# ESP32_with_USBC.net
KiCad netlist of a schematic drawn in Altium Designer
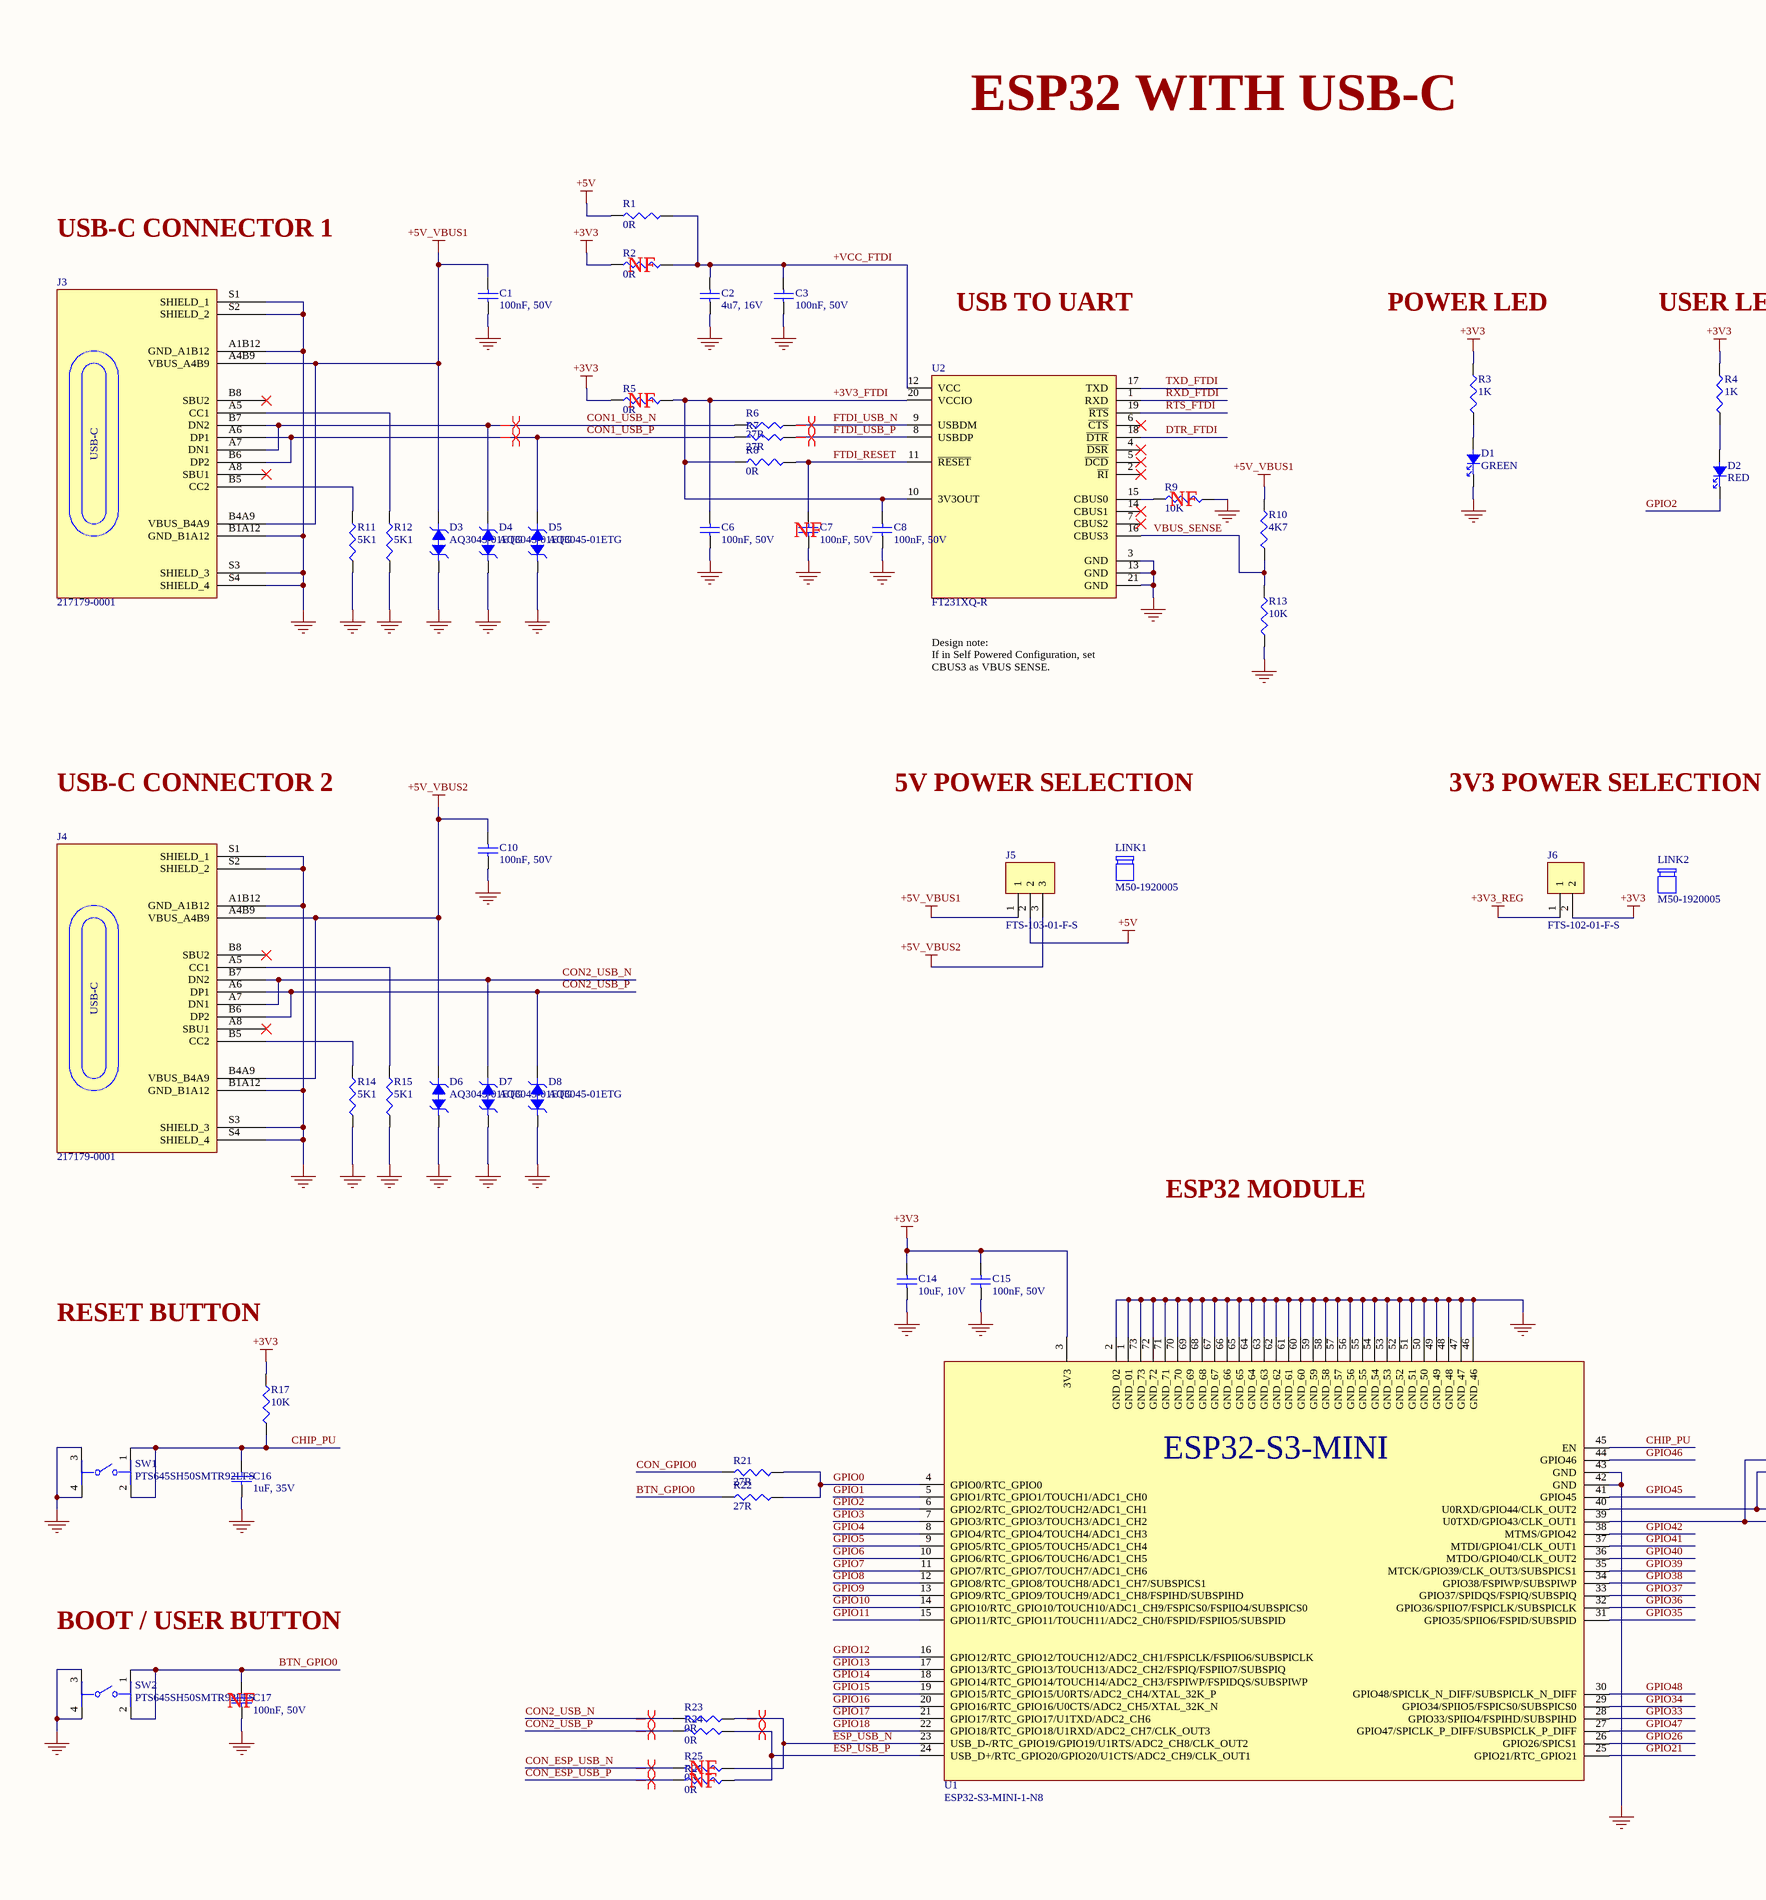
[diagram p0: ESP32 with USBC.SchDoc, left]
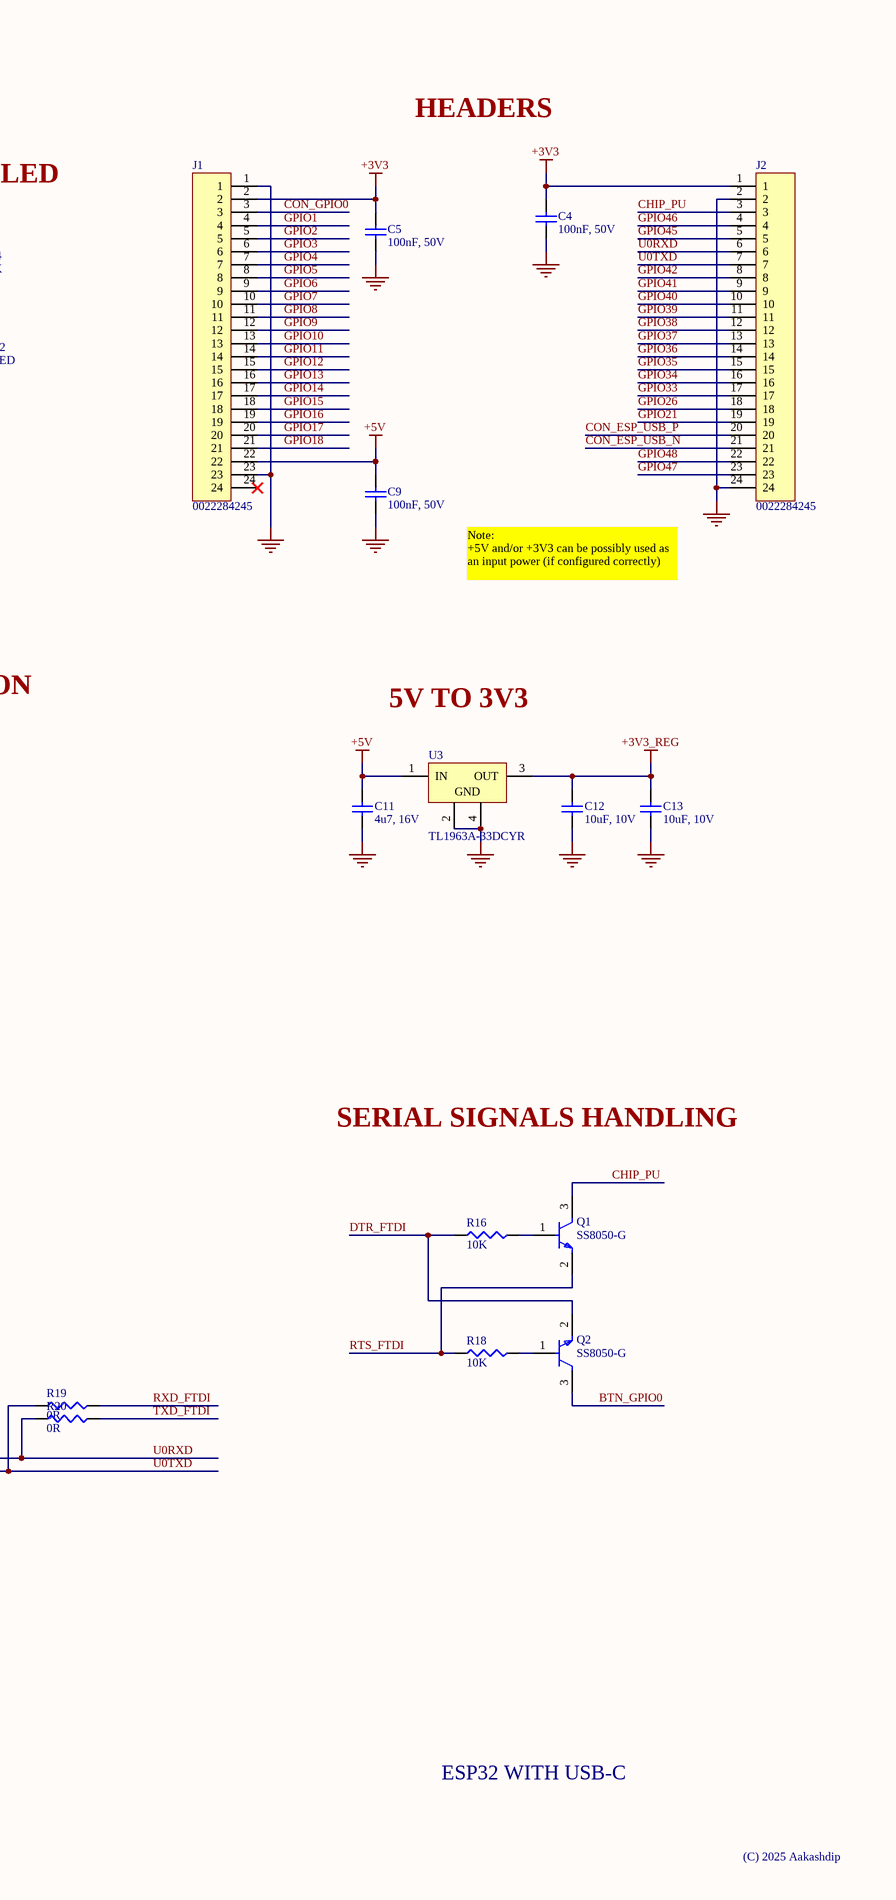
[diagram p1: ESP32 with USBC.SchDoc, right]

(export (version "E")
  (design (tool "Eeschema 10.0.6"))
  (components
    (comp (ref "C1")
      (value "100nF, 50V")
      (footprint "CAPC1005X55N")
      (description "CAP CER 0.1UF 50V X7R 0402")
      (fields
        (field (name "MANUFACTURER") "Samsung")
        (field (name "MANUFACTURER PART NUMBER") "CL05B104KB54PNC")
      )
      (libsource (lib "Schlib") (part "CL05B104KB54PNC"))
    )
    (comp (ref "C2")
      (value "4u7, 16V")
      (footprint "CAPC1005X55N")
      (description "CAP CER 4.7UF 16V X5R 0402")
      (fields
        (field (name "MANUFACTURER") "Samsung")
        (field (name "MANUFACTURER PART NUMBER") "CL05A475MO5NUNC")
      )
      (libsource (lib "Schlib") (part "CL05A475MO5NUNC"))
    )
    (comp (ref "C3")
      (value "100nF, 50V")
      (footprint "CAPC1005X55N")
      (description "CAP CER 0.1UF 50V X7R 0402")
      (fields
        (field (name "MANUFACTURER") "Samsung")
        (field (name "MANUFACTURER PART NUMBER") "CL05B104KB54PNC")
      )
      (libsource (lib "Schlib") (part "CL05B104KB54PNC"))
    )
    (comp (ref "C4")
      (value "100nF, 50V")
      (footprint "CAPC1005X55N")
      (description "CAP CER 0.1UF 50V X7R 0402")
      (fields
        (field (name "MANUFACTURER") "Samsung")
        (field (name "MANUFACTURER PART NUMBER") "CL05B104KB54PNC")
      )
      (libsource (lib "Schlib") (part "CL05B104KB54PNC"))
    )
    (comp (ref "C5")
      (value "100nF, 50V")
      (footprint "CAPC1005X55N")
      (description "CAP CER 0.1UF 50V X7R 0402")
      (fields
        (field (name "MANUFACTURER") "Samsung")
        (field (name "MANUFACTURER PART NUMBER") "CL05B104KB54PNC")
      )
      (libsource (lib "Schlib") (part "CL05B104KB54PNC"))
    )
    (comp (ref "C6")
      (value "100nF, 50V")
      (footprint "CAPC1005X55N")
      (description "CAP CER 0.1UF 50V X7R 0402")
      (fields
        (field (name "MANUFACTURER") "Samsung")
        (field (name "MANUFACTURER PART NUMBER") "CL05B104KB54PNC")
      )
      (libsource (lib "Schlib") (part "CL05B104KB54PNC"))
    )
    (comp (ref "C7")
      (value "100nF, 50V")
      (footprint "CAPC1005X55N")
      (description "CAP CER 0.1UF 50V X7R 0402")
      (fields
        (field (name "MANUFACTURER") "Samsung")
        (field (name "MANUFACTURER PART NUMBER") "CL05B104KB54PNC")
      )
      (libsource (lib "Schlib") (part "CL05B104KB54PNC"))
    )
    (comp (ref "C8")
      (value "100nF, 50V")
      (footprint "CAPC1005X55N")
      (description "CAP CER 0.1UF 50V X7R 0402")
      (fields
        (field (name "MANUFACTURER") "Samsung")
        (field (name "MANUFACTURER PART NUMBER") "CL05B104KB54PNC")
      )
      (libsource (lib "Schlib") (part "CL05B104KB54PNC"))
    )
    (comp (ref "C9")
      (value "100nF, 50V")
      (footprint "CAPC1005X55N")
      (description "CAP CER 0.1UF 50V X7R 0402")
      (fields
        (field (name "MANUFACTURER") "Samsung")
        (field (name "MANUFACTURER PART NUMBER") "CL05B104KB54PNC")
      )
      (libsource (lib "Schlib") (part "CL05B104KB54PNC"))
    )
    (comp (ref "C10")
      (value "100nF, 50V")
      (footprint "CAPC1005X55N")
      (description "CAP CER 0.1UF 50V X7R 0402")
      (fields
        (field (name "MANUFACTURER") "Samsung")
        (field (name "MANUFACTURER PART NUMBER") "CL05B104KB54PNC")
      )
      (libsource (lib "Schlib") (part "CL05B104KB54PNC"))
    )
    (comp (ref "C11")
      (value "4u7, 16V")
      (footprint "CAPC1005X55N")
      (description "CAP CER 4.7UF 16V X5R 0402")
      (fields
        (field (name "MANUFACTURER") "Samsung")
        (field (name "MANUFACTURER PART NUMBER") "CL05A475MO5NUNC")
      )
      (libsource (lib "Schlib") (part "CL05A475MO5NUNC"))
    )
    (comp (ref "C12")
      (value "10uF, 10V")
      (footprint "CAPC1005X55N")
      (description "CAP CER 10UF 10V X5R 0402")
      (fields
        (field (name "MANUFACTURER") "Samsung")
        (field (name "MANUFACTURER PART NUMBER") "CL05A106MP8NUB8")
      )
      (libsource (lib "Schlib") (part "CL05A106MP8NUB8"))
    )
    (comp (ref "C13")
      (value "10uF, 10V")
      (footprint "CAPC1005X55N")
      (description "CAP CER 10UF 10V X5R 0402")
      (fields
        (field (name "MANUFACTURER") "Samsung")
        (field (name "MANUFACTURER PART NUMBER") "CL05A106MP8NUB8")
      )
      (libsource (lib "Schlib") (part "CL05A106MP8NUB8"))
    )
    (comp (ref "C14")
      (value "10uF, 10V")
      (footprint "CAPC1005X55N")
      (description "CAP CER 10UF 10V X5R 0402")
      (fields
        (field (name "MANUFACTURER") "Samsung")
        (field (name "MANUFACTURER PART NUMBER") "CL05A106MP8NUB8")
      )
      (libsource (lib "Schlib") (part "CL05A106MP8NUB8"))
    )
    (comp (ref "C15")
      (value "100nF, 50V")
      (footprint "CAPC1005X55N")
      (description "CAP CER 0.1UF 50V X7R 0402")
      (fields
        (field (name "MANUFACTURER") "Samsung")
        (field (name "MANUFACTURER PART NUMBER") "CL05B104KB54PNC")
      )
      (libsource (lib "Schlib") (part "CL05B104KB54PNC"))
    )
    (comp (ref "C16")
      (value "1uF, 35V")
      (footprint "CAPC1005X55N")
      (description "CAP CER 1UF 35V X5R 0402")
      (fields
        (field (name "MANUFACTURER") "Samsung")
        (field (name "MANUFACTURER PART NUMBER") "CL05A105KL5NRNC")
      )
      (libsource (lib "Schlib") (part "CL05A105KL5NRNC"))
    )
    (comp (ref "C17")
      (value "100nF, 50V")
      (footprint "CAPC1005X55N")
      (description "CAP CER 0.1UF 50V X7R 0402")
      (fields
        (field (name "MANUFACTURER") "Samsung")
        (field (name "MANUFACTURER PART NUMBER") "CL05B104KB54PNC")
      )
      (libsource (lib "Schlib") (part "CL05B104KB54PNC"))
    )
    (comp (ref "D1")
      (value "GREEN")
      (footprint "LED0402G")
      (description "LED YLW-GRN 0402 SMD")
      (fields
        (field (name "MANUFACTURER") "Vishay")
        (field (name "MANUFACTURER PART NUMBER") "VLMG1500-GS08")
      )
      (libsource (lib "Schlib") (part "VLMG1500-GS08"))
    )
    (comp (ref "D2")
      (value "RED")
      (footprint "LED0402R")
      (description "LED RED 0402 SMD")
      (fields
        (field (name "MANUFACTURER") "Vishay")
        (field (name "MANUFACTURER PART NUMBER") "VLMS1500-GS08")
      )
      (libsource (lib "Schlib") (part "VLMS1500-GS08"))
    )
    (comp (ref "D3")
      (value "AQ3045-01ETG")
      (footprint "SOD882")
      (description "TVS DIODE 5.3VWM 12VC SOD882")
      (fields (field (name "MANUFACTURER") "Littelfuse") (field (name "LCSC PART NUMBER") "C3710326"))
      (libsource (lib "Schlib") (part "AQ3045-01ETG"))
    )
    (comp (ref "D4")
      (value "AQ3045-01ETG")
      (footprint "SOD882")
      (description "TVS DIODE 5.3VWM 12VC SOD882")
      (fields (field (name "MANUFACTURER") "Littelfuse") (field (name "LCSC PART NUMBER") "C3710326"))
      (libsource (lib "Schlib") (part "AQ3045-01ETG"))
    )
    (comp (ref "D5")
      (value "AQ3045-01ETG")
      (footprint "SOD882")
      (description "TVS DIODE 5.3VWM 12VC SOD882")
      (fields (field (name "MANUFACTURER") "Littelfuse") (field (name "LCSC PART NUMBER") "C3710326"))
      (libsource (lib "Schlib") (part "AQ3045-01ETG"))
    )
    (comp (ref "D6")
      (value "AQ3045-01ETG")
      (footprint "SOD882")
      (description "TVS DIODE 5.3VWM 12VC SOD882")
      (fields (field (name "MANUFACTURER") "Littelfuse") (field (name "LCSC PART NUMBER") "C3710326"))
      (libsource (lib "Schlib") (part "AQ3045-01ETG"))
    )
    (comp (ref "D7")
      (value "AQ3045-01ETG")
      (footprint "SOD882")
      (description "TVS DIODE 5.3VWM 12VC SOD882")
      (fields (field (name "MANUFACTURER") "Littelfuse") (field (name "LCSC PART NUMBER") "C3710326"))
      (libsource (lib "Schlib") (part "AQ3045-01ETG"))
    )
    (comp (ref "D8")
      (value "AQ3045-01ETG")
      (footprint "SOD882")
      (description "TVS DIODE 5.3VWM 12VC SOD882")
      (fields (field (name "MANUFACTURER") "Littelfuse") (field (name "LCSC PART NUMBER") "C3710326"))
      (libsource (lib "Schlib") (part "AQ3045-01ETG"))
    )
    (comp (ref "J1")
      (value "0022284245")
      (footprint "HDR_1X24_2.54MM")
      (description "CONN HEADER VERT 24POS 2.54MM")
      (fields (field (name "MANUFACTURER") "Molex") (field (name "LCSC PART NUMBER") "C7145888"))
      (libsource (lib "Schlib") (part "0022284245"))
    )
    (comp (ref "J2")
      (value "0022284245")
      (footprint "HDR_1X24_2.54MM")
      (description "CONN HEADER VERT 24POS 2.54MM")
      (fields (field (name "MANUFACTURER") "Molex") (field (name "LCSC PART NUMBER") "C7145888"))
      (libsource (lib "") (part "0022284245_1"))
    )
    (comp (ref "J3")
      (value "217179-0001")
      (footprint "FP-2171790001-MFG")
      (description "CONN RCP USB2.0 TYP C 24P SMD RA")
      (fields (field (name "MANUFACTURER") "Molex") (field (name "LCSC PART NUMBER") "C3197684"))
      (libsource (lib "Schlib") (part "217179-0001"))
    )
    (comp (ref "J4")
      (value "217179-0001")
      (footprint "FP-2171790001-MFG")
      (description "CONN RCP USB2.0 TYP C 24P SMD RA")
      (fields (field (name "MANUFACTURER") "Molex") (field (name "LCSC PART NUMBER") "C3197684"))
      (libsource (lib "Schlib") (part "217179-0001"))
    )
    (comp (ref "J5")
      (value "FTS-103-01-F-S")
      (footprint "HDR_1X3_1.27MM")
      (description "CONN HEADER VERT 3POS 1.27MM")
      (fields (field (name "MANUFACTURER") "Samtec") (field (name "LCSC PART NUMBER") "C3333578"))
      (libsource (lib "Schlib") (part "FTS-103-01-F-S"))
    )
    (comp (ref "J6")
      (value "FTS-102-01-F-S")
      (footprint "HDR_1X2_1.27MM")
      (description "CONN HEADER VERT 2POS 1.27MM")
      (fields (field (name "MANUFACTURER") "Samtec") (field (name "LCSC PART NUMBER") "C6045317"))
      (libsource (lib "Schlib") (part "FTS-102-01-F-S"))
    )
    (comp (ref "LINK1")
      (value "M50-1920005")
      (description "CONN SHUNT 1.27MM RED")
      (fields (field (name "MANUFACTURER") "Harwin") (field (name "LCSC PART NUMBER") "C6985646"))
      (libsource (lib "Schlib") (part "M50-1920005"))
    )
    (comp (ref "LINK2")
      (value "M50-1920005")
      (description "CONN SHUNT 1.27MM RED")
      (fields (field (name "MANUFACTURER") "Harwin") (field (name "LCSC PART NUMBER") "C6985646"))
      (libsource (lib "Schlib") (part "M50-1920005"))
    )
    (comp (ref "Q1")
      (value "SS8050-G")
      (footprint "FP-SS8050-G-IPC_B")
      (description "TRANS NPN 25V 1.5A SOT23-3")
      (fields (field (name "MANUFACTURER") "Comchip") (field (name "LCSC PART NUMBER") "C164886"))
      (libsource (lib "Schlib") (part "SS8050-G"))
    )
    (comp (ref "Q2")
      (value "SS8050-G")
      (footprint "FP-SS8050-G-IPC_B")
      (description "TRANS NPN 25V 1.5A SOT23-3")
      (fields (field (name "MANUFACTURER") "Comchip") (field (name "LCSC PART NUMBER") "C164886"))
      (libsource (lib "Schlib") (part "SS8050-G"))
    )
    (comp (ref "R1")
      (value "0R")
      (footprint "RESC1005X37N")
      (description "RES 0 OHM JUMPER 1/16W 0402")
      (fields
        (field (name "MANUFACTURER") "Yageo")
        (field (name "MANUFACTURER PART NUMBER") "RC0402JR-070RL")
      )
      (libsource (lib "Schlib") (part "RC0402JR-070RL"))
    )
    (comp (ref "R2")
      (value "0R")
      (footprint "RESC1005X37N")
      (description "RES 0 OHM JUMPER 1/16W 0402")
      (fields
        (field (name "MANUFACTURER") "Yageo")
        (field (name "MANUFACTURER PART NUMBER") "RC0402JR-070RL")
      )
      (libsource (lib "Schlib") (part "RC0402JR-070RL"))
    )
    (comp (ref "R3")
      (value "1K")
      (footprint "RESC1005X37N")
      (description "RES 1K OHM 1% 1/16W 0402")
      (fields
        (field (name "MANUFACTURER") "Yageo")
        (field (name "MANUFACTURER PART NUMBER") "RC0402FR-071KL")
      )
      (libsource (lib "Schlib") (part "RC0402FR-071KL"))
    )
    (comp (ref "R4")
      (value "1K")
      (footprint "RESC1005X37N")
      (description "RES 1K OHM 1% 1/16W 0402")
      (fields
        (field (name "MANUFACTURER") "Yageo")
        (field (name "MANUFACTURER PART NUMBER") "RC0402FR-071KL")
      )
      (libsource (lib "Schlib") (part "RC0402FR-071KL"))
    )
    (comp (ref "R5")
      (value "0R")
      (footprint "RESC1005X37N")
      (description "RES 0 OHM JUMPER 1/16W 0402")
      (fields
        (field (name "MANUFACTURER") "Yageo")
        (field (name "MANUFACTURER PART NUMBER") "RC0402JR-070RL")
      )
      (libsource (lib "Schlib") (part "RC0402JR-070RL"))
    )
    (comp (ref "R6")
      (value "27R")
      (footprint "RESC1005X37N")
      (description "RES 27 OHM 1% 1/16W 0402")
      (fields
        (field (name "MANUFACTURER") "Yageo")
        (field (name "MANUFACTURER PART NUMBER") "RC0402FR-0727RL")
      )
      (libsource (lib "Schlib") (part "RC0402FR-0727RL"))
    )
    (comp (ref "R7")
      (value "27R")
      (footprint "RESC1005X37N")
      (description "RES 27 OHM 1% 1/16W 0402")
      (fields
        (field (name "MANUFACTURER") "Yageo")
        (field (name "MANUFACTURER PART NUMBER") "RC0402FR-0727RL")
      )
      (libsource (lib "Schlib") (part "RC0402FR-0727RL"))
    )
    (comp (ref "R8")
      (value "0R")
      (footprint "RESC1005X37N")
      (description "RES 0 OHM JUMPER 1/16W 0402")
      (fields
        (field (name "MANUFACTURER") "Yageo")
        (field (name "MANUFACTURER PART NUMBER") "RC0402JR-070RL")
      )
      (libsource (lib "Schlib") (part "RC0402JR-070RL"))
    )
    (comp (ref "R9")
      (value "10K")
      (footprint "RESC1005X37N")
      (description "RES SMD 10K OHM 1% 1/16W 0402")
      (fields
        (field (name "MANUFACTURER") "Yageo")
        (field (name "MANUFACTURER PART NUMBER") "AC0402FR-0710KL")
      )
      (libsource (lib "Schlib") (part "AC0402FR-0710KL"))
    )
    (comp (ref "R10")
      (value "4K7")
      (footprint "RESC1005X37N")
      (description "RES 4.7K OHM 1% 1/16W 0402")
      (fields
        (field (name "MANUFACTURER") "Yageo")
        (field (name "MANUFACTURER PART NUMBER") "RC0402FR-074K7L")
      )
      (libsource (lib "Schlib") (part "RC0402FR-074K7L"))
    )
    (comp (ref "R11")
      (value "5K1")
      (footprint "RESC1005X37N")
      (description "RES SMD 5.1K OHM 1% 1/16W 0402")
      (fields
        (field (name "MANUFACTURER") "Yageo")
        (field (name "MANUFACTURER PART NUMBER") "AC0402FR-075K1L")
      )
      (libsource (lib "Schlib") (part "AC0402FR-075K1L"))
    )
    (comp (ref "R12")
      (value "5K1")
      (footprint "RESC1005X37N")
      (description "RES SMD 5.1K OHM 1% 1/16W 0402")
      (fields
        (field (name "MANUFACTURER") "Yageo")
        (field (name "MANUFACTURER PART NUMBER") "AC0402FR-075K1L")
      )
      (libsource (lib "Schlib") (part "AC0402FR-075K1L"))
    )
    (comp (ref "R13")
      (value "10K")
      (footprint "RESC1005X37N")
      (description "RES SMD 10K OHM 1% 1/16W 0402")
      (fields
        (field (name "MANUFACTURER") "Yageo")
        (field (name "MANUFACTURER PART NUMBER") "AC0402FR-0710KL")
      )
      (libsource (lib "Schlib") (part "AC0402FR-0710KL"))
    )
    (comp (ref "R14")
      (value "5K1")
      (footprint "RESC1005X37N")
      (description "RES SMD 5.1K OHM 1% 1/16W 0402")
      (fields
        (field (name "MANUFACTURER") "Yageo")
        (field (name "MANUFACTURER PART NUMBER") "AC0402FR-075K1L")
      )
      (libsource (lib "Schlib") (part "AC0402FR-075K1L"))
    )
    (comp (ref "R15")
      (value "5K1")
      (footprint "RESC1005X37N")
      (description "RES SMD 5.1K OHM 1% 1/16W 0402")
      (fields
        (field (name "MANUFACTURER") "Yageo")
        (field (name "MANUFACTURER PART NUMBER") "AC0402FR-075K1L")
      )
      (libsource (lib "Schlib") (part "AC0402FR-075K1L"))
    )
    (comp (ref "R16")
      (value "10K")
      (footprint "RESC1005X37N")
      (description "RES SMD 10K OHM 1% 1/16W 0402")
      (fields
        (field (name "MANUFACTURER") "Yageo")
        (field (name "MANUFACTURER PART NUMBER") "AC0402FR-0710KL")
      )
      (libsource (lib "Schlib") (part "AC0402FR-0710KL"))
    )
    (comp (ref "R17")
      (value "10K")
      (footprint "RESC1005X37N")
      (description "RES SMD 10K OHM 1% 1/16W 0402")
      (fields
        (field (name "MANUFACTURER") "Yageo")
        (field (name "MANUFACTURER PART NUMBER") "AC0402FR-0710KL")
      )
      (libsource (lib "Schlib") (part "AC0402FR-0710KL"))
    )
    (comp (ref "R18")
      (value "10K")
      (footprint "RESC1005X37N")
      (description "RES SMD 10K OHM 1% 1/16W 0402")
      (fields
        (field (name "MANUFACTURER") "Yageo")
        (field (name "MANUFACTURER PART NUMBER") "AC0402FR-0710KL")
      )
      (libsource (lib "Schlib") (part "AC0402FR-0710KL"))
    )
    (comp (ref "R19")
      (value "0R")
      (footprint "RESC1005X37N")
      (description "RES 0 OHM JUMPER 1/16W 0402")
      (fields
        (field (name "MANUFACTURER") "Yageo")
        (field (name "MANUFACTURER PART NUMBER") "RC0402JR-070RL")
      )
      (libsource (lib "Schlib") (part "RC0402JR-070RL"))
    )
    (comp (ref "R20")
      (value "0R")
      (footprint "RESC1005X37N")
      (description "RES 0 OHM JUMPER 1/16W 0402")
      (fields
        (field (name "MANUFACTURER") "Yageo")
        (field (name "MANUFACTURER PART NUMBER") "RC0402JR-070RL")
      )
      (libsource (lib "Schlib") (part "RC0402JR-070RL"))
    )
    (comp (ref "R21")
      (value "27R")
      (footprint "RESC1005X37N")
      (description "RES 27 OHM 1% 1/16W 0402")
      (fields
        (field (name "MANUFACTURER") "Yageo")
        (field (name "MANUFACTURER PART NUMBER") "RC0402FR-0727RL")
      )
      (libsource (lib "Schlib") (part "RC0402FR-0727RL"))
    )
    (comp (ref "R22")
      (value "27R")
      (footprint "RESC1005X37N")
      (description "RES 27 OHM 1% 1/16W 0402")
      (fields
        (field (name "MANUFACTURER") "Yageo")
        (field (name "MANUFACTURER PART NUMBER") "RC0402FR-0727RL")
      )
      (libsource (lib "Schlib") (part "RC0402FR-0727RL"))
    )
    (comp (ref "R23")
      (value "0R")
      (footprint "RESC1005X37N")
      (description "RES 0 OHM JUMPER 1/16W 0402")
      (fields
        (field (name "MANUFACTURER") "Yageo")
        (field (name "MANUFACTURER PART NUMBER") "RC0402JR-070RL")
      )
      (libsource (lib "Schlib") (part "RC0402JR-070RL"))
    )
    (comp (ref "R24")
      (value "0R")
      (footprint "RESC1005X37N")
      (description "RES 0 OHM JUMPER 1/16W 0402")
      (fields
        (field (name "MANUFACTURER") "Yageo")
        (field (name "MANUFACTURER PART NUMBER") "RC0402JR-070RL")
      )
      (libsource (lib "Schlib") (part "RC0402JR-070RL"))
    )
    (comp (ref "R25")
      (value "0R")
      (footprint "RESC1005X37N")
      (description "RES 0 OHM JUMPER 1/16W 0402")
      (fields
        (field (name "MANUFACTURER") "Yageo")
        (field (name "MANUFACTURER PART NUMBER") "RC0402JR-070RL")
      )
      (libsource (lib "Schlib") (part "RC0402JR-070RL"))
    )
    (comp (ref "R26")
      (value "0R")
      (footprint "RESC1005X37N")
      (description "RES 0 OHM JUMPER 1/16W 0402")
      (fields
        (field (name "MANUFACTURER") "Yageo")
        (field (name "MANUFACTURER PART NUMBER") "RC0402JR-070RL")
      )
      (libsource (lib "Schlib") (part "RC0402JR-070RL"))
    )
    (comp (ref "SW1")
      (value "PTS645SH50SMTR92LFS")
      (footprint "FP-PTS645SH50SMTR92LFS-MFG")
      (description "SWITCH TACTILE SPST-NO 0.05A 12V")
      (fields (field (name "MANUFACTURER") "ITT C&K") (field (name "LCSC PART NUMBER") "C221869"))
      (libsource (lib "Schlib") (part "PTS645SH50SMTR92LFS"))
    )
    (comp (ref "SW2")
      (value "PTS645SH50SMTR92LFS")
      (footprint "FP-PTS645SH50SMTR92LFS-MFG")
      (description "SWITCH TACTILE SPST-NO 0.05A 12V")
      (fields (field (name "MANUFACTURER") "ITT C&K") (field (name "LCSC PART NUMBER") "C221869"))
      (libsource (lib "Schlib") (part "PTS645SH50SMTR92LFS"))
    )
    (comp (ref "U1")
      (value "ESP32-S3-MINI-1-N8")
      (footprint "XCVR_ESP32-S3-MINI-1-N8")
      (description "SMD Module, ESP32-S3FN8, 8 mb Sp")
      (fields (field (name "MANUFACTURER") "Espressif Systems") (field (name "LCSC PART NUMBER") "C2913206"))
      (libsource (lib "Schlib") (part "ESP32-S3-MINI-1-N8"))
    )
    (comp (ref "U2")
      (value "FT231XQ-R")
      (footprint "FP-QFN-20-IPC_B")
      (description "IC USB SERIAL FULL UART 20QFN")
      (fields (field (name "MANUFACTURER") "FTDI") (field (name "LCSC PART NUMBER") "C132159"))
      (libsource (lib "Schlib") (part "FT231XQ-R"))
    )
    (comp (ref "U3")
      (value "TL1963A-33DCYR")
      (footprint "DCY0004A_N")
      (description "IC REG LINEAR 3.3V 1.5A SOT223-4")
      (fields (field (name "MANUFACTURER") "Texas Instruments") (field (name "LCSC PART NUMBER") "C181262"))
      (libsource (lib "Schlib") (part "TL1963A-33DCYR"))
    )
  )
  (nets
    (net (code "1") (name "+3V3") (class "Default")
      (node (ref "C14") (pin "2") (pinfunction "2_2") (pintype "passive"))
      (node (ref "C15") (pin "2") (pinfunction "2_2") (pintype "passive"))
      (node (ref "C4") (pin "2") (pinfunction "2_2") (pintype "passive"))
      (node (ref "C5") (pin "2") (pinfunction "2_2") (pintype "passive"))
      (node (ref "J1") (pin "2") (pinfunction "2_2") (pintype "passive"))
      (node (ref "J2") (pin "1") (pinfunction "1_1") (pintype "passive"))
      (node (ref "J6") (pin "2") (pinfunction "2_2") (pintype "passive"))
      (node (ref "R17") (pin "2") (pinfunction "2_2") (pintype "passive"))
      (node (ref "R2") (pin "1") (pinfunction "1_1") (pintype "passive"))
      (node (ref "R3") (pin "2") (pinfunction "2_2") (pintype "passive"))
      (node (ref "R4") (pin "2") (pinfunction "2_2") (pintype "passive"))
      (node (ref "R5") (pin "1") (pinfunction "1_1") (pintype "passive"))
      (node (ref "U1") (pin "3") (pinfunction "3V3_3") (pintype "passive"))
    )
    (net (code "2") (name "+3V3_REG") (class "Default")
      (node (ref "C12") (pin "2") (pinfunction "2_2") (pintype "passive"))
      (node (ref "C13") (pin "2") (pinfunction "2_2") (pintype "passive"))
      (node (ref "J6") (pin "1") (pinfunction "1_1") (pintype "passive"))
      (node (ref "U3") (pin "3") (pinfunction "OUT_3") (pintype "power_in"))
    )
    (net (code "3") (name "+5V") (class "Default")
      (node (ref "C11") (pin "2") (pinfunction "2_2") (pintype "passive"))
      (node (ref "C9") (pin "2") (pinfunction "2_2") (pintype "passive"))
      (node (ref "J1") (pin "22") (pinfunction "22_22") (pintype "passive"))
      (node (ref "J5") (pin "2") (pinfunction "2_2") (pintype "passive"))
      (node (ref "R1") (pin "1") (pinfunction "1_1") (pintype "passive"))
      (node (ref "U3") (pin "1") (pinfunction "IN_1") (pintype "power_in"))
    )
    (net (code "4") (name "+5V_VBUS1") (class "Default")
      (node (ref "C1") (pin "2") (pinfunction "2_2") (pintype "passive"))
      (node (ref "D3") (pin "2") (pinfunction "2_2") (pintype "passive"))
      (node (ref "J3") (pin "A4B9") (pinfunction "VBUS_A4B9_A4B9") (pintype "passive"))
      (node (ref "J3") (pin "B4A9") (pinfunction "VBUS_B4A9_B4A9") (pintype "passive"))
      (node (ref "J5") (pin "1") (pinfunction "1_1") (pintype "passive"))
      (node (ref "R10") (pin "2") (pinfunction "2_2") (pintype "passive"))
    )
    (net (code "5") (name "+5V_VBUS2") (class "Default")
      (node (ref "C10") (pin "2") (pinfunction "2_2") (pintype "passive"))
      (node (ref "D6") (pin "2") (pinfunction "2_2") (pintype "passive"))
      (node (ref "J4") (pin "A4B9") (pinfunction "VBUS_A4B9_A4B9") (pintype "passive"))
      (node (ref "J4") (pin "B4A9") (pinfunction "VBUS_B4A9_B4A9") (pintype "passive"))
      (node (ref "J5") (pin "3") (pinfunction "3_3") (pintype "passive"))
    )
    (net (code "6") (name "/+3V3_FTDI") (class "Default")
      (node (ref "C6") (pin "2") (pinfunction "2_2") (pintype "passive"))
      (node (ref "C8") (pin "2") (pinfunction "2_2") (pintype "passive"))
      (node (ref "R5") (pin "2") (pinfunction "2_2") (pintype "passive"))
      (node (ref "R8") (pin "1") (pinfunction "1_1") (pintype "passive"))
      (node (ref "U2") (pin "10") (pinfunction "3V3OUT_10") (pintype "passive"))
      (node (ref "U2") (pin "20") (pinfunction "VCCIO_20") (pintype "passive"))
    )
    (net (code "7") (name "/+VCC_FTDI") (class "Default")
      (node (ref "C2") (pin "2") (pinfunction "2_2") (pintype "passive"))
      (node (ref "C3") (pin "2") (pinfunction "2_2") (pintype "passive"))
      (node (ref "R1") (pin "2") (pinfunction "2_2") (pintype "passive"))
      (node (ref "R2") (pin "2") (pinfunction "2_2") (pintype "passive"))
      (node (ref "U2") (pin "12") (pinfunction "VCC_12") (pintype "passive"))
    )
    (net (code "8") (name "/BTN_GPIO0") (class "Default")
      (node (ref "C17") (pin "2") (pinfunction "2_2") (pintype "passive"))
      (node (ref "Q2") (pin "3") (pinfunction "C_3") (pintype "passive"))
      (node (ref "R22") (pin "1") (pinfunction "1_1") (pintype "passive"))
      (node (ref "SW2") (pin "1") (pinfunction "1_1") (pintype "passive"))
      (node (ref "SW2") (pin "2") (pinfunction "2_2") (pintype "passive"))
    )
    (net (code "9") (name "/CHIP_PU") (class "Default")
      (node (ref "C16") (pin "2") (pinfunction "2_2") (pintype "passive"))
      (node (ref "J2") (pin "3") (pinfunction "3_3") (pintype "passive"))
      (node (ref "Q1") (pin "3") (pinfunction "C_3") (pintype "passive"))
      (node (ref "R17") (pin "1") (pinfunction "1_1") (pintype "passive"))
      (node (ref "SW1") (pin "1") (pinfunction "1_1") (pintype "passive"))
      (node (ref "SW1") (pin "2") (pinfunction "2_2") (pintype "passive"))
      (node (ref "U1") (pin "45") (pinfunction "EN_45") (pintype "passive"))
    )
    (net (code "10") (name "/CON1_USB_N") (class "Default")
      (node (ref "D4") (pin "2") (pinfunction "2_2") (pintype "passive"))
      (node (ref "J3") (pin "A7") (pinfunction "DN1_A7") (pintype "passive"))
      (node (ref "J3") (pin "B7") (pinfunction "DN2_B7") (pintype "passive"))
      (node (ref "R6") (pin "1") (pinfunction "1_1") (pintype "passive"))
    )
    (net (code "11") (name "/CON1_USB_P") (class "Default")
      (node (ref "D5") (pin "2") (pinfunction "2_2") (pintype "passive"))
      (node (ref "J3") (pin "A6") (pinfunction "DP1_A6") (pintype "passive"))
      (node (ref "J3") (pin "B6") (pinfunction "DP2_B6") (pintype "passive"))
      (node (ref "R7") (pin "1") (pinfunction "1_1") (pintype "passive"))
    )
    (net (code "12") (name "/CON2_USB_N") (class "Default")
      (node (ref "D7") (pin "2") (pinfunction "2_2") (pintype "passive"))
      (node (ref "J4") (pin "A7") (pinfunction "DN1_A7") (pintype "passive"))
      (node (ref "J4") (pin "B7") (pinfunction "DN2_B7") (pintype "passive"))
      (node (ref "R23") (pin "1") (pinfunction "1_1") (pintype "passive"))
    )
    (net (code "13") (name "/CON2_USB_P") (class "Default")
      (node (ref "D8") (pin "2") (pinfunction "2_2") (pintype "passive"))
      (node (ref "J4") (pin "A6") (pinfunction "DP1_A6") (pintype "passive"))
      (node (ref "J4") (pin "B6") (pinfunction "DP2_B6") (pintype "passive"))
      (node (ref "R24") (pin "1") (pinfunction "1_1") (pintype "passive"))
    )
    (net (code "14") (name "/CON_ESP_USB_N") (class "Default")
      (node (ref "J2") (pin "21") (pinfunction "21_21") (pintype "passive"))
      (node (ref "R25") (pin "1") (pinfunction "1_1") (pintype "passive"))
    )
    (net (code "15") (name "/CON_ESP_USB_P") (class "Default")
      (node (ref "J2") (pin "20") (pinfunction "20_20") (pintype "passive"))
      (node (ref "R26") (pin "1") (pinfunction "1_1") (pintype "passive"))
    )
    (net (code "16") (name "/CON_GPIO0") (class "Default")
      (node (ref "J1") (pin "3") (pinfunction "3_3") (pintype "passive"))
      (node (ref "R21") (pin "1") (pinfunction "1_1") (pintype "passive"))
    )
    (net (code "17") (name "/DTR_FTDI") (class "Default")
      (node (ref "Q2") (pin "2") (pinfunction "E_2") (pintype "passive"))
      (node (ref "R16") (pin "1") (pinfunction "1_1") (pintype "passive"))
      (node (ref "U2") (pin "18") (pinfunction "~{DTR}_18") (pintype "passive"))
    )
    (net (code "18") (name "/ESP_USB_N") (class "Default")
      (node (ref "R23") (pin "2") (pinfunction "2_2") (pintype "passive"))
      (node (ref "R25") (pin "2") (pinfunction "2_2") (pintype "passive"))
      (node (ref "U1") (pin "23") (pinfunction "USB_D-/RTC_GPIO19/GPIO19/U1RTS/ADC2_CH8/CLK_OUT2_23") (pintype "passive"))
    )
    (net (code "19") (name "/ESP_USB_P") (class "Default")
      (node (ref "R24") (pin "2") (pinfunction "2_2") (pintype "passive"))
      (node (ref "R26") (pin "2") (pinfunction "2_2") (pintype "passive"))
      (node (ref "U1") (pin "24") (pinfunction "USB_D+/RTC_GPIO20/GPIO20/U1CTS/ADC2_CH9/CLK_OUT1_24") (pintype "passive"))
    )
    (net (code "20") (name "/FTDI_RESET") (class "Default")
      (node (ref "C7") (pin "2") (pinfunction "2_2") (pintype "passive"))
      (node (ref "R8") (pin "2") (pinfunction "2_2") (pintype "passive"))
      (node (ref "U2") (pin "11") (pinfunction "~{RESET}_11") (pintype "passive"))
    )
    (net (code "21") (name "/FTDI_USB_N") (class "Default")
      (node (ref "R6") (pin "2") (pinfunction "2_2") (pintype "passive"))
      (node (ref "U2") (pin "9") (pinfunction "USBDM_9") (pintype "passive"))
    )
    (net (code "22") (name "/FTDI_USB_P") (class "Default")
      (node (ref "R7") (pin "2") (pinfunction "2_2") (pintype "passive"))
      (node (ref "U2") (pin "8") (pinfunction "USBDP_8") (pintype "passive"))
    )
    (net (code "23") (name "/GPIO0") (class "Default")
      (node (ref "R21") (pin "2") (pinfunction "2_2") (pintype "passive"))
      (node (ref "R22") (pin "2") (pinfunction "2_2") (pintype "passive"))
      (node (ref "U1") (pin "4") (pinfunction "GPIO0/RTC_GPIO0_4") (pintype "passive"))
    )
    (net (code "24") (name "/GPIO1") (class "Default")
      (node (ref "J1") (pin "4") (pinfunction "4_4") (pintype "passive"))
      (node (ref "U1") (pin "5") (pinfunction "GPIO1/RTC_GPIO1/TOUCH1/ADC1_CH0_5") (pintype "passive"))
    )
    (net (code "25") (name "/GPIO2") (class "Default")
      (node (ref "D2") (pin "1") (pinfunction "1_1") (pintype "passive"))
      (node (ref "J1") (pin "5") (pinfunction "5_5") (pintype "passive"))
      (node (ref "U1") (pin "6") (pinfunction "GPIO2/RTC_GPIO2/TOUCH2/ADC1_CH1_6") (pintype "passive"))
    )
    (net (code "26") (name "/GPIO3") (class "Default")
      (node (ref "J1") (pin "6") (pinfunction "6_6") (pintype "passive"))
      (node (ref "U1") (pin "7") (pinfunction "GPIO3/RTC_GPIO3/TOUCH3/ADC1_CH2_7") (pintype "passive"))
    )
    (net (code "27") (name "/GPIO4") (class "Default")
      (node (ref "J1") (pin "7") (pinfunction "7_7") (pintype "passive"))
      (node (ref "U1") (pin "8") (pinfunction "GPIO4/RTC_GPIO4/TOUCH4/ADC1_CH3_8") (pintype "passive"))
    )
    (net (code "28") (name "/GPIO5") (class "Default")
      (node (ref "J1") (pin "8") (pinfunction "8_8") (pintype "passive"))
      (node (ref "U1") (pin "9") (pinfunction "GPIO5/RTC_GPIO5/TOUCH5/ADC1_CH4_9") (pintype "passive"))
    )
    (net (code "29") (name "/GPIO6") (class "Default")
      (node (ref "J1") (pin "9") (pinfunction "9_9") (pintype "passive"))
      (node (ref "U1") (pin "10") (pinfunction "GPIO6/RTC_GPIO6/TOUCH6/ADC1_CH5_10") (pintype "passive"))
    )
    (net (code "30") (name "/GPIO7") (class "Default")
      (node (ref "J1") (pin "10") (pinfunction "10_10") (pintype "passive"))
      (node (ref "U1") (pin "11") (pinfunction "GPIO7/RTC_GPIO7/TOUCH7/ADC1_CH6_11") (pintype "passive"))
    )
    (net (code "31") (name "/GPIO8") (class "Default")
      (node (ref "J1") (pin "11") (pinfunction "11_11") (pintype "passive"))
      (node (ref "U1") (pin "12") (pinfunction "GPIO8/RTC_GPIO8/TOUCH8/ADC1_CH7/SUBSPICS1_12") (pintype "passive"))
    )
    (net (code "32") (name "/GPIO9") (class "Default")
      (node (ref "J1") (pin "12") (pinfunction "12_12") (pintype "passive"))
      (node (ref "U1") (pin "13") (pinfunction "GPIO9/RTC_GPIO9/TOUCH9/ADC1_CH8/FSPIHD/SUBSPIHD_13") (pintype "passive"))
    )
    (net (code "33") (name "/GPIO10") (class "Default")
      (node (ref "J1") (pin "13") (pinfunction "13_13") (pintype "passive"))
      (node (ref "U1") (pin "14") (pinfunction "GPIO10/RTC_GPIO10/TOUCH10/ADC1_CH9/FSPICS0/FSPIIO4/SUBSPICS0_14") (pintype "passive"))
    )
    (net (code "34") (name "/GPIO11") (class "Default")
      (node (ref "J1") (pin "14") (pinfunction "14_14") (pintype "passive"))
      (node (ref "U1") (pin "15") (pinfunction "GPIO11/RTC_GPIO11/TOUCH11/ADC2_CH0/FSPID/FSPIIO5/SUBSPID_15") (pintype "passive"))
    )
    (net (code "35") (name "/GPIO12") (class "Default")
      (node (ref "J1") (pin "15") (pinfunction "15_15") (pintype "passive"))
      (node (ref "U1") (pin "16") (pinfunction "GPIO12/RTC_GPIO12/TOUCH12/ADC2_CH1/FSPICLK/FSPIIO6/SUBSPICLK_16") (pintype "passive"))
    )
    (net (code "36") (name "/GPIO13") (class "Default")
      (node (ref "J1") (pin "16") (pinfunction "16_16") (pintype "passive"))
      (node (ref "U1") (pin "17") (pinfunction "GPIO13/RTC_GPIO13/TOUCH13/ADC2_CH2/FSPIQ/FSPIIO7/SUBSPIQ_17") (pintype "passive"))
    )
    (net (code "37") (name "/GPIO14") (class "Default")
      (node (ref "J1") (pin "17") (pinfunction "17_17") (pintype "passive"))
      (node (ref "U1") (pin "18") (pinfunction "GPIO14/RTC_GPIO14/TOUCH14/ADC2_CH3/FSPIWP/FSPIDQS/SUBSPIWP_18") (pintype "passive"))
    )
    (net (code "38") (name "/GPIO15") (class "Default")
      (node (ref "J1") (pin "18") (pinfunction "18_18") (pintype "passive"))
      (node (ref "U1") (pin "19") (pinfunction "GPIO15/RTC_GPIO15/U0RTS/ADC2_CH4/XTAL_32K_P_19") (pintype "passive"))
    )
    (net (code "39") (name "/GPIO16") (class "Default")
      (node (ref "J1") (pin "19") (pinfunction "19_19") (pintype "passive"))
      (node (ref "U1") (pin "20") (pinfunction "GPIO16/RTC_GPIO16/U0CTS/ADC2_CH5/XTAL_32K_N_20") (pintype "passive"))
    )
    (net (code "40") (name "/GPIO17") (class "Default")
      (node (ref "J1") (pin "20") (pinfunction "20_20") (pintype "passive"))
      (node (ref "U1") (pin "21") (pinfunction "GPIO17/RTC_GPIO17/U1TXD/ADC2_CH6_21") (pintype "passive"))
    )
    (net (code "41") (name "/GPIO18") (class "Default")
      (node (ref "J1") (pin "21") (pinfunction "21_21") (pintype "passive"))
      (node (ref "U1") (pin "22") (pinfunction "GPIO18/RTC_GPIO18/U1RXD/ADC2_CH7/CLK_OUT3_22") (pintype "passive"))
    )
    (net (code "42") (name "/GPIO21") (class "Default")
      (node (ref "J2") (pin "19") (pinfunction "19_19") (pintype "passive"))
      (node (ref "U1") (pin "25") (pinfunction "GPIO21/RTC_GPIO21_25") (pintype "passive"))
    )
    (net (code "43") (name "/GPIO26") (class "Default")
      (node (ref "J2") (pin "18") (pinfunction "18_18") (pintype "passive"))
      (node (ref "U1") (pin "26") (pinfunction "GPIO26/SPICS1_26") (pintype "passive"))
    )
    (net (code "44") (name "/GPIO33") (class "Default")
      (node (ref "J2") (pin "17") (pinfunction "17_17") (pintype "passive"))
      (node (ref "U1") (pin "28") (pinfunction "GPIO33/SPIIO4/FSPIHD/SUBSPIHD_28") (pintype "passive"))
    )
    (net (code "45") (name "/GPIO34") (class "Default")
      (node (ref "J2") (pin "16") (pinfunction "16_16") (pintype "passive"))
      (node (ref "U1") (pin "29") (pinfunction "GPIO34/SPIIO5/FSPICS0/SUBSPICS0_29") (pintype "passive"))
    )
    (net (code "46") (name "/GPIO35") (class "Default")
      (node (ref "J2") (pin "15") (pinfunction "15_15") (pintype "passive"))
      (node (ref "U1") (pin "31") (pinfunction "GPIO35/SPIIO6/FSPID/SUBSPID_31") (pintype "passive"))
    )
    (net (code "47") (name "/GPIO36") (class "Default")
      (node (ref "J2") (pin "14") (pinfunction "14_14") (pintype "passive"))
      (node (ref "U1") (pin "32") (pinfunction "GPIO36/SPIIO7/FSPICLK/SUBSPICLK_32") (pintype "passive"))
    )
    (net (code "48") (name "/GPIO37") (class "Default")
      (node (ref "J2") (pin "13") (pinfunction "13_13") (pintype "passive"))
      (node (ref "U1") (pin "33") (pinfunction "GPIO37/SPIDQS/FSPIQ/SUBSPIQ_33") (pintype "passive"))
    )
    (net (code "49") (name "/GPIO38") (class "Default")
      (node (ref "J2") (pin "12") (pinfunction "12_12") (pintype "passive"))
      (node (ref "U1") (pin "34") (pinfunction "GPIO38/FSPIWP/SUBSPIWP_34") (pintype "passive"))
    )
    (net (code "50") (name "/GPIO39") (class "Default")
      (node (ref "J2") (pin "11") (pinfunction "11_11") (pintype "passive"))
      (node (ref "U1") (pin "35") (pinfunction "MTCK/GPIO39/CLK_OUT3/SUBSPICS1_35") (pintype "passive"))
    )
    (net (code "51") (name "/GPIO40") (class "Default")
      (node (ref "J2") (pin "10") (pinfunction "10_10") (pintype "passive"))
      (node (ref "U1") (pin "36") (pinfunction "MTDO/GPIO40/CLK_OUT2_36") (pintype "passive"))
    )
    (net (code "52") (name "/GPIO41") (class "Default")
      (node (ref "J2") (pin "9") (pinfunction "9_9") (pintype "passive"))
      (node (ref "U1") (pin "37") (pinfunction "MTDI/GPIO41/CLK_OUT1_37") (pintype "passive"))
    )
    (net (code "53") (name "/GPIO42") (class "Default")
      (node (ref "J2") (pin "8") (pinfunction "8_8") (pintype "passive"))
      (node (ref "U1") (pin "38") (pinfunction "MTMS/GPIO42_38") (pintype "passive"))
    )
    (net (code "54") (name "/GPIO45") (class "Default")
      (node (ref "J2") (pin "5") (pinfunction "5_5") (pintype "passive"))
      (node (ref "U1") (pin "41") (pinfunction "GPIO45_41") (pintype "passive"))
    )
    (net (code "55") (name "/GPIO46") (class "Default")
      (node (ref "J2") (pin "4") (pinfunction "4_4") (pintype "passive"))
      (node (ref "U1") (pin "44") (pinfunction "GPIO46_44") (pintype "passive"))
    )
    (net (code "56") (name "/GPIO47") (class "Default")
      (node (ref "J2") (pin "23") (pinfunction "23_23") (pintype "passive"))
      (node (ref "U1") (pin "27") (pinfunction "GPIO47/SPICLK_P_DIFF/SUBSPICLK_P_DIFF_27") (pintype "passive"))
    )
    (net (code "57") (name "/GPIO48") (class "Default")
      (node (ref "J2") (pin "22") (pinfunction "22_22") (pintype "passive"))
      (node (ref "U1") (pin "30") (pinfunction "GPIO48/SPICLK_N_DIFF/SUBSPICLK_N_DIFF_30") (pintype "passive"))
    )
    (net (code "58") (name "/RTS_FTDI") (class "Default")
      (node (ref "Q1") (pin "2") (pinfunction "E_2") (pintype "passive"))
      (node (ref "R18") (pin "1") (pinfunction "1_1") (pintype "passive"))
      (node (ref "U2") (pin "19") (pinfunction "~{RTS}_19") (pintype "passive"))
    )
    (net (code "59") (name "/RXD_FTDI") (class "Default")
      (node (ref "R19") (pin "2") (pinfunction "2_2") (pintype "passive"))
      (node (ref "U2") (pin "1") (pinfunction "RXD_1") (pintype "passive"))
    )
    (net (code "60") (name "/TXD_FTDI") (class "Default")
      (node (ref "R20") (pin "2") (pinfunction "2_2") (pintype "passive"))
      (node (ref "U2") (pin "17") (pinfunction "TXD_17") (pintype "passive"))
    )
    (net (code "61") (name "/U0RXD") (class "Default")
      (node (ref "J2") (pin "6") (pinfunction "6_6") (pintype "passive"))
      (node (ref "R20") (pin "1") (pinfunction "1_1") (pintype "passive"))
      (node (ref "U1") (pin "40") (pinfunction "U0RXD/GPIO44/CLK_OUT2_40") (pintype "passive"))
    )
    (net (code "62") (name "/U0TXD") (class "Default")
      (node (ref "J2") (pin "7") (pinfunction "7_7") (pintype "passive"))
      (node (ref "R19") (pin "1") (pinfunction "1_1") (pintype "passive"))
      (node (ref "U1") (pin "39") (pinfunction "U0TXD/GPIO43/CLK_OUT1_39") (pintype "passive"))
    )
    (net (code "63") (name "/VBUS_SENSE") (class "Default")
      (node (ref "R10") (pin "1") (pinfunction "1_1") (pintype "passive"))
      (node (ref "R13") (pin "1") (pinfunction "1_1") (pintype "passive"))
      (node (ref "U2") (pin "16") (pinfunction "CBUS3_16") (pintype "passive"))
    )
    (net (code "64") (name "GND") (class "Default")
      (node (ref "C1") (pin "1") (pinfunction "1_1") (pintype "passive"))
      (node (ref "C10") (pin "1") (pinfunction "1_1") (pintype "passive"))
      (node (ref "C11") (pin "1") (pinfunction "1_1") (pintype "passive"))
      (node (ref "C12") (pin "1") (pinfunction "1_1") (pintype "passive"))
      (node (ref "C13") (pin "1") (pinfunction "1_1") (pintype "passive"))
      (node (ref "C14") (pin "1") (pinfunction "1_1") (pintype "passive"))
      (node (ref "C15") (pin "1") (pinfunction "1_1") (pintype "passive"))
      (node (ref "C16") (pin "1") (pinfunction "1_1") (pintype "passive"))
      (node (ref "C17") (pin "1") (pinfunction "1_1") (pintype "passive"))
      (node (ref "C2") (pin "1") (pinfunction "1_1") (pintype "passive"))
      (node (ref "C3") (pin "1") (pinfunction "1_1") (pintype "passive"))
      (node (ref "C4") (pin "1") (pinfunction "1_1") (pintype "passive"))
      (node (ref "C5") (pin "1") (pinfunction "1_1") (pintype "passive"))
      (node (ref "C6") (pin "1") (pinfunction "1_1") (pintype "passive"))
      (node (ref "C7") (pin "1") (pinfunction "1_1") (pintype "passive"))
      (node (ref "C8") (pin "1") (pinfunction "1_1") (pintype "passive"))
      (node (ref "C9") (pin "1") (pinfunction "1_1") (pintype "passive"))
      (node (ref "D1") (pin "1") (pinfunction "1_1") (pintype "passive"))
      (node (ref "D3") (pin "1") (pinfunction "1_1") (pintype "passive"))
      (node (ref "D4") (pin "1") (pinfunction "1_1") (pintype "passive"))
      (node (ref "D5") (pin "1") (pinfunction "1_1") (pintype "passive"))
      (node (ref "D6") (pin "1") (pinfunction "1_1") (pintype "passive"))
      (node (ref "D7") (pin "1") (pinfunction "1_1") (pintype "passive"))
      (node (ref "D8") (pin "1") (pinfunction "1_1") (pintype "passive"))
      (node (ref "J1") (pin "1") (pinfunction "1_1") (pintype "passive"))
      (node (ref "J1") (pin "23") (pinfunction "23_23") (pintype "passive"))
      (node (ref "J2") (pin "2") (pinfunction "2_2") (pintype "passive"))
      (node (ref "J2") (pin "24") (pinfunction "24_24") (pintype "passive"))
      (node (ref "J3") (pin "A1B12") (pinfunction "GND_A1B12_A1B12") (pintype "passive"))
      (node (ref "J3") (pin "B1A12") (pinfunction "GND_B1A12_B1A12") (pintype "passive"))
      (node (ref "J3") (pin "S1") (pinfunction "SHIELD_1_S1") (pintype "passive"))
      (node (ref "J3") (pin "S2") (pinfunction "SHIELD_2_S2") (pintype "passive"))
      (node (ref "J3") (pin "S3") (pinfunction "SHIELD_3_S3") (pintype "passive"))
      (node (ref "J3") (pin "S4") (pinfunction "SHIELD_4_S4") (pintype "passive"))
      (node (ref "J4") (pin "A1B12") (pinfunction "GND_A1B12_A1B12") (pintype "passive"))
      (node (ref "J4") (pin "B1A12") (pinfunction "GND_B1A12_B1A12") (pintype "passive"))
      (node (ref "J4") (pin "S1") (pinfunction "SHIELD_1_S1") (pintype "passive"))
      (node (ref "J4") (pin "S2") (pinfunction "SHIELD_2_S2") (pintype "passive"))
      (node (ref "J4") (pin "S3") (pinfunction "SHIELD_3_S3") (pintype "passive"))
      (node (ref "J4") (pin "S4") (pinfunction "SHIELD_4_S4") (pintype "passive"))
      (node (ref "R11") (pin "1") (pinfunction "1_1") (pintype "passive"))
      (node (ref "R12") (pin "1") (pinfunction "1_1") (pintype "passive"))
      (node (ref "R13") (pin "2") (pinfunction "2_2") (pintype "passive"))
      (node (ref "R14") (pin "1") (pinfunction "1_1") (pintype "passive"))
      (node (ref "R15") (pin "1") (pinfunction "1_1") (pintype "passive"))
      (node (ref "R9") (pin "2") (pinfunction "2_2") (pintype "passive"))
      (node (ref "SW1") (pin "3") (pinfunction "3_3") (pintype "passive"))
      (node (ref "SW1") (pin "4") (pinfunction "4_4") (pintype "passive"))
      (node (ref "SW2") (pin "3") (pinfunction "3_3") (pintype "passive"))
      (node (ref "SW2") (pin "4") (pinfunction "4_4") (pintype "passive"))
      (node (ref "U1") (pin "1") (pinfunction "GND_01_1") (pintype "passive"))
      (node (ref "U1") (pin "2") (pinfunction "GND_02_2") (pintype "passive"))
      (node (ref "U1") (pin "42") (pinfunction "GND_42") (pintype "passive"))
      (node (ref "U1") (pin "43") (pinfunction "GND_43") (pintype "passive"))
      (node (ref "U1") (pin "46") (pinfunction "GND_46_46") (pintype "passive"))
      (node (ref "U1") (pin "47") (pinfunction "GND_47_47") (pintype "passive"))
      (node (ref "U1") (pin "48") (pinfunction "GND_48_48") (pintype "passive"))
      (node (ref "U1") (pin "49") (pinfunction "GND_49_49") (pintype "passive"))
      (node (ref "U1") (pin "50") (pinfunction "GND_50_50") (pintype "passive"))
      (node (ref "U1") (pin "51") (pinfunction "GND_51_51") (pintype "passive"))
      (node (ref "U1") (pin "52") (pinfunction "GND_52_52") (pintype "passive"))
      (node (ref "U1") (pin "53") (pinfunction "GND_53_53") (pintype "passive"))
      (node (ref "U1") (pin "54") (pinfunction "GND_54_54") (pintype "passive"))
      (node (ref "U1") (pin "55") (pinfunction "GND_55_55") (pintype "passive"))
      (node (ref "U1") (pin "56") (pinfunction "GND_56_56") (pintype "passive"))
      (node (ref "U1") (pin "57") (pinfunction "GND_57_57") (pintype "passive"))
      (node (ref "U1") (pin "58") (pinfunction "GND_58_58") (pintype "passive"))
      (node (ref "U1") (pin "59") (pinfunction "GND_59_59") (pintype "passive"))
      (node (ref "U1") (pin "60") (pinfunction "GND_60_60") (pintype "passive"))
      (node (ref "U1") (pin "61") (pinfunction "GND_61_61") (pintype "passive"))
      (node (ref "U1") (pin "62") (pinfunction "GND_62_62") (pintype "passive"))
      (node (ref "U1") (pin "63") (pinfunction "GND_63_63") (pintype "passive"))
      (node (ref "U1") (pin "64") (pinfunction "GND_64_64") (pintype "passive"))
      (node (ref "U1") (pin "65") (pinfunction "GND_65_65") (pintype "passive"))
      (node (ref "U1") (pin "66") (pinfunction "GND_66_66") (pintype "passive"))
      (node (ref "U1") (pin "67") (pinfunction "GND_67_67") (pintype "passive"))
      (node (ref "U1") (pin "68") (pinfunction "GND_68_68") (pintype "passive"))
      (node (ref "U1") (pin "69") (pinfunction "GND_69_69") (pintype "passive"))
      (node (ref "U1") (pin "70") (pinfunction "GND_70_70") (pintype "passive"))
      (node (ref "U1") (pin "71") (pinfunction "GND_71_71") (pintype "passive"))
      (node (ref "U1") (pin "72") (pinfunction "GND_72_72") (pintype "passive"))
      (node (ref "U1") (pin "73") (pinfunction "GND_73_73") (pintype "passive"))
      (node (ref "U2") (pin "13") (pinfunction "GND_13") (pintype "passive"))
      (node (ref "U2") (pin "21") (pinfunction "GND_21") (pintype "passive"))
      (node (ref "U2") (pin "3") (pinfunction "GND_3") (pintype "passive"))
      (node (ref "U3") (pin "2") (pinfunction "GND_2") (pintype "power_in"))
      (node (ref "U3") (pin "4") (pinfunction "GND_4") (pintype "power_in"))
    )
    (net (code "65") (name "Net-(D1-Pad2)") (class "Default")
      (node (ref "D1") (pin "2") (pinfunction "2_2") (pintype "passive"))
      (node (ref "R3") (pin "1") (pinfunction "1_1") (pintype "passive"))
    )
    (net (code "66") (name "Net-(D2-Pad2)") (class "Default")
      (node (ref "D2") (pin "2") (pinfunction "2_2") (pintype "passive"))
      (node (ref "R4") (pin "1") (pinfunction "1_1") (pintype "passive"))
    )
    (net (code "67") (name "Net-(J3-CC1)") (class "Default")
      (node (ref "J3") (pin "A5") (pinfunction "CC1_A5") (pintype "passive"))
      (node (ref "R12") (pin "2") (pinfunction "2_2") (pintype "passive"))
    )
    (net (code "68") (name "Net-(J3-CC2)") (class "Default")
      (node (ref "J3") (pin "B5") (pinfunction "CC2_B5") (pintype "passive"))
      (node (ref "R11") (pin "2") (pinfunction "2_2") (pintype "passive"))
    )
    (net (code "69") (name "Net-(J4-CC1)") (class "Default")
      (node (ref "J4") (pin "A5") (pinfunction "CC1_A5") (pintype "passive"))
      (node (ref "R15") (pin "2") (pinfunction "2_2") (pintype "passive"))
    )
    (net (code "70") (name "Net-(J4-CC2)") (class "Default")
      (node (ref "J4") (pin "B5") (pinfunction "CC2_B5") (pintype "passive"))
      (node (ref "R14") (pin "2") (pinfunction "2_2") (pintype "passive"))
    )
    (net (code "71") (name "Net-(Q1-B)") (class "Default")
      (node (ref "Q1") (pin "1") (pinfunction "B_1") (pintype "passive"))
      (node (ref "R16") (pin "2") (pinfunction "2_2") (pintype "passive"))
    )
    (net (code "72") (name "Net-(Q2-B)") (class "Default")
      (node (ref "Q2") (pin "1") (pinfunction "B_1") (pintype "passive"))
      (node (ref "R18") (pin "2") (pinfunction "2_2") (pintype "passive"))
    )
    (net (code "73") (name "Net-(U2-CBUS0)") (class "Default")
      (node (ref "R9") (pin "1") (pinfunction "1_1") (pintype "passive"))
      (node (ref "U2") (pin "15") (pinfunction "CBUS0_15") (pintype "passive"))
    )
    (net (code "74") (name "unconnected-(J1-Pad24)") (class "Default")
      (node (ref "J1") (pin "24") (pinfunction "24_24") (pintype "passive+no_connect"))
    )
    (net (code "75") (name "unconnected-(J3-SBU1-PadA8)") (class "Default")
      (node (ref "J3") (pin "A8") (pinfunction "SBU1_A8") (pintype "passive+no_connect"))
    )
    (net (code "76") (name "unconnected-(J3-SBU2-PadB8)") (class "Default")
      (node (ref "J3") (pin "B8") (pinfunction "SBU2_B8") (pintype "passive+no_connect"))
    )
    (net (code "77") (name "unconnected-(J4-SBU1-PadA8)") (class "Default")
      (node (ref "J4") (pin "A8") (pinfunction "SBU1_A8") (pintype "passive+no_connect"))
    )
    (net (code "78") (name "unconnected-(J4-SBU2-PadB8)") (class "Default")
      (node (ref "J4") (pin "B8") (pinfunction "SBU2_B8") (pintype "passive+no_connect"))
    )
    (net (code "79") (name "unconnected-(U2-CBUS1-Pad14)") (class "Default")
      (node (ref "U2") (pin "14") (pinfunction "CBUS1_14") (pintype "passive+no_connect"))
    )
    (net (code "80") (name "unconnected-(U2-CBUS2-Pad7)") (class "Default")
      (node (ref "U2") (pin "7") (pinfunction "CBUS2_7") (pintype "passive+no_connect"))
    )
    (net (code "81") (name "unconnected-(U2-~{CTS}-Pad6)") (class "Default")
      (node (ref "U2") (pin "6") (pinfunction "~{CTS}_6") (pintype "passive+no_connect"))
    )
    (net (code "82") (name "unconnected-(U2-~{DCD}-Pad5)") (class "Default")
      (node (ref "U2") (pin "5") (pinfunction "~{DCD}_5") (pintype "passive+no_connect"))
    )
    (net (code "83") (name "unconnected-(U2-~{DSR}-Pad4)") (class "Default")
      (node (ref "U2") (pin "4") (pinfunction "~{DSR}_4") (pintype "passive+no_connect"))
    )
    (net (code "84") (name "unconnected-(U2-~{RI}-Pad2)") (class "Default")
      (node (ref "U2") (pin "2") (pinfunction "~{RI}_2") (pintype "passive+no_connect"))
    )
  )
)
